# ph_for_cadizv41_pcbv0.net
KiCad netlist of a schematic drawn in EAGLE
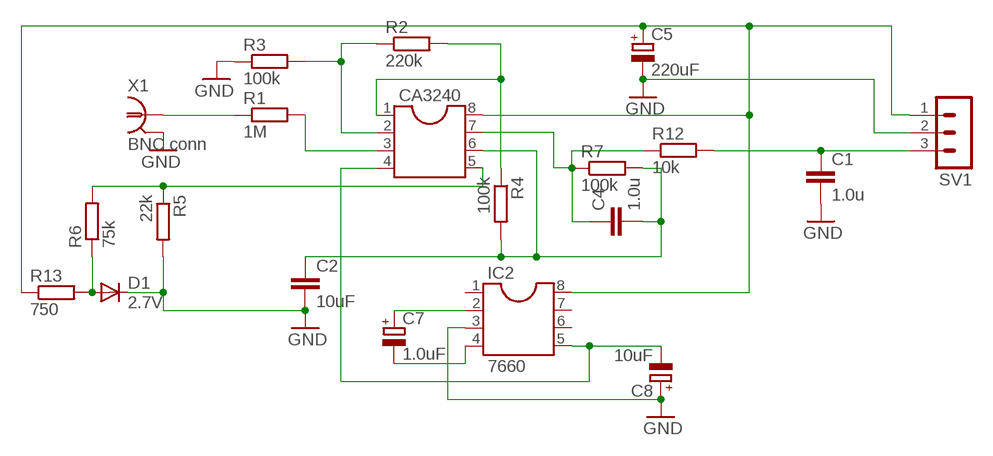
[diagram p0: schematic, sheet 1]

(export (version "E")
  (design (tool "Eeschema 10.0.6"))
  (components
    (comp (ref "C1")
      (value "1.0u")
      (footprint "eagle-import:C102-043X133")
      (libsource (lib "eagle-import") (part "C-EU102-043X133"))
    )
    (comp (ref "C2")
      (value "10uF")
      (footprint "eagle-import:C102-043X133")
      (libsource (lib "eagle-import") (part "C-EU102-043X133"))
    )
    (comp (ref "C4")
      (value "1.0u")
      (footprint "eagle-import:C102-043X133")
      (libsource (lib "eagle-import") (part "C-EU102-043X133"))
    )
    (comp (ref "C5")
      (value "220uF")
      (footprint "eagle-import:E5-6")
      (libsource (lib "eagle-import") (part "CPOL-EUE5-6"))
    )
    (comp (ref "C7")
      (value "1.0uF")
      (footprint "eagle-import:E5-6")
      (libsource (lib "eagle-import") (part "CPOL-EUE5-6"))
    )
    (comp (ref "C8")
      (value "10uF")
      (footprint "eagle-import:E5-6")
      (libsource (lib "eagle-import") (part "CPOL-EUE5-6"))
    )
    (comp (ref "CA3240")
      (value "DIL8")
      (footprint "eagle-import:DIL08")
      (libsource (lib "eagle-import") (part "DIL8"))
    )
    (comp (ref "D1")
      (value "2.7V")
      (footprint "eagle-import:DO35-7")
      (libsource (lib "eagle-import") (part "1N4148DO35-7"))
    )
    (comp (ref "IC2")
      (value "7660")
      (footprint "eagle-import:DIL08")
      (libsource (lib "eagle-import") (part "DIL8"))
    )
    (comp (ref "R1")
      (value "1M")
      (footprint "eagle-import:0207_12")
      (libsource (lib "eagle-import") (part "R-EU_0207/12"))
    )
    (comp (ref "R2")
      (value "220k")
      (footprint "eagle-import:0207_12")
      (libsource (lib "eagle-import") (part "R-EU_0207/12"))
    )
    (comp (ref "R3")
      (value "100k")
      (footprint "eagle-import:0207_12")
      (libsource (lib "eagle-import") (part "R-EU_0207/12"))
    )
    (comp (ref "R4")
      (value "100k")
      (footprint "eagle-import:0207_12")
      (libsource (lib "eagle-import") (part "R-EU_0207/12"))
    )
    (comp (ref "R5")
      (value "22k")
      (footprint "eagle-import:0207_12")
      (libsource (lib "eagle-import") (part "R-EU_0207/12"))
    )
    (comp (ref "R6")
      (value "75k")
      (footprint "eagle-import:0207_12")
      (libsource (lib "eagle-import") (part "R-EU_0207/12"))
    )
    (comp (ref "R7")
      (value "100k")
      (footprint "eagle-import:0207_12")
      (libsource (lib "eagle-import") (part "R-EU_0207/12"))
    )
    (comp (ref "R12")
      (value "10k")
      (footprint "eagle-import:0207_12")
      (libsource (lib "eagle-import") (part "R-EU_0207/12"))
    )
    (comp (ref "R13")
      (value "750")
      (footprint "eagle-import:0207_12")
      (libsource (lib "eagle-import") (part "R-EU_0207/12"))
    )
    (comp (ref "SV1")
      (value "MA03-1")
      (footprint "eagle-import:MA03-1")
      (libsource (lib "eagle-import") (part "MA03-1"))
    )
    (comp (ref "X1")
      (value "BNC conn")
      (footprint "eagle-import:R141426")
      (fields (field (name "MF") "FARNELL") (field (name "MPN") "R141426161"))
      (libsource (lib "eagle-import") (part "R141426"))
    )
  )
  (nets
    (net (code "1") (name "GND") (class "Default")
      (node (ref "C1") (pin "2") (pinfunction "2_2") (pintype "passive"))
      (node (ref "C2") (pin "2") (pinfunction "2_2") (pintype "passive"))
      (node (ref "C5") (pin "-") (pinfunction "-_-") (pintype "passive"))
      (node (ref "C8") (pin "+") (pinfunction "+_+") (pintype "passive"))
      (node (ref "D1") (pin "C") (pinfunction "C_C") (pintype "passive"))
      (node (ref "IC2") (pin "3") (pinfunction "3_3") (pintype "passive"))
      (node (ref "R3") (pin "1") (pinfunction "1_1") (pintype "passive"))
      (node (ref "R5") (pin "2") (pinfunction "2_2") (pintype "passive"))
      (node (ref "SV1") (pin "2") (pinfunction "2_2") (pintype "passive"))
      (node (ref "X1") (pin "2") (pinfunction "GND_2") (pintype "power_in"))
    )
    (net (code "2") (name "Net-(C1-Pad1)") (class "Default")
      (node (ref "C1") (pin "1") (pinfunction "1_1") (pintype "passive"))
      (node (ref "R12") (pin "2") (pinfunction "2_2") (pintype "passive"))
      (node (ref "SV1") (pin "3") (pinfunction "3_3") (pintype "passive"))
    )
    (net (code "3") (name "Net-(C2-Pad1)") (class "Default")
      (node (ref "C2") (pin "1") (pinfunction "1_1") (pintype "passive"))
      (node (ref "C4") (pin "2") (pinfunction "2_2") (pintype "passive"))
      (node (ref "CA3240") (pin "6") (pinfunction "6_6") (pintype "passive"))
      (node (ref "R4") (pin "2") (pinfunction "2_2") (pintype "passive"))
      (node (ref "R7") (pin "2") (pinfunction "2_2") (pintype "passive"))
    )
    (net (code "4") (name "Net-(C4-Pad1)") (class "Default")
      (node (ref "C4") (pin "1") (pinfunction "1_1") (pintype "passive"))
      (node (ref "CA3240") (pin "7") (pinfunction "7_7") (pintype "passive"))
      (node (ref "R12") (pin "1") (pinfunction "1_1") (pintype "passive"))
      (node (ref "R7") (pin "1") (pinfunction "1_1") (pintype "passive"))
    )
    (net (code "5") (name "Net-(C5-Pad+)") (class "Default")
      (node (ref "C5") (pin "+") (pinfunction "+_+") (pintype "passive"))
      (node (ref "CA3240") (pin "8") (pinfunction "8_8") (pintype "passive"))
      (node (ref "IC2") (pin "8") (pinfunction "8_8") (pintype "passive"))
      (node (ref "R13") (pin "1") (pinfunction "1_1") (pintype "passive"))
      (node (ref "SV1") (pin "1") (pinfunction "1_1") (pintype "passive"))
    )
    (net (code "6") (name "Net-(C7-Pad+)") (class "Default")
      (node (ref "C7") (pin "+") (pinfunction "+_+") (pintype "passive"))
      (node (ref "IC2") (pin "2") (pinfunction "2_2") (pintype "passive"))
    )
    (net (code "7") (name "Net-(C7-Pad-)") (class "Default")
      (node (ref "C7") (pin "-") (pinfunction "-_-") (pintype "passive"))
      (node (ref "IC2") (pin "4") (pinfunction "4_4") (pintype "passive"))
    )
    (net (code "8") (name "Net-(C8-Pad-)") (class "Default")
      (node (ref "C8") (pin "-") (pinfunction "-_-") (pintype "passive"))
      (node (ref "CA3240") (pin "4") (pinfunction "4_4") (pintype "passive"))
      (node (ref "IC2") (pin "5") (pinfunction "5_5") (pintype "passive"))
    )
    (net (code "9") (name "Net-(CA3240-Pad1)") (class "Default")
      (node (ref "CA3240") (pin "1") (pinfunction "1_1") (pintype "passive"))
      (node (ref "R2") (pin "2") (pinfunction "2_2") (pintype "passive"))
      (node (ref "R4") (pin "1") (pinfunction "1_1") (pintype "passive"))
    )
    (net (code "10") (name "Net-(CA3240-Pad2)") (class "Default")
      (node (ref "CA3240") (pin "2") (pinfunction "2_2") (pintype "passive"))
      (node (ref "R2") (pin "1") (pinfunction "1_1") (pintype "passive"))
      (node (ref "R3") (pin "2") (pinfunction "2_2") (pintype "passive"))
    )
    (net (code "11") (name "Net-(CA3240-Pad3)") (class "Default")
      (node (ref "CA3240") (pin "3") (pinfunction "3_3") (pintype "passive"))
      (node (ref "R1") (pin "2") (pinfunction "2_2") (pintype "passive"))
    )
    (net (code "12") (name "Net-(CA3240-Pad5)") (class "Default")
      (node (ref "CA3240") (pin "5") (pinfunction "5_5") (pintype "passive"))
      (node (ref "R5") (pin "1") (pinfunction "1_1") (pintype "passive"))
      (node (ref "R6") (pin "2") (pinfunction "2_2") (pintype "passive"))
    )
    (net (code "13") (name "Net-(D1-PadA)") (class "Default")
      (node (ref "D1") (pin "A") (pinfunction "A_A") (pintype "passive"))
      (node (ref "R13") (pin "2") (pinfunction "2_2") (pintype "passive"))
      (node (ref "R6") (pin "1") (pinfunction "1_1") (pintype "passive"))
    )
    (net (code "14") (name "Net-(R1-Pad1)") (class "Default")
      (node (ref "R1") (pin "1") (pinfunction "1_1") (pintype "passive"))
      (node (ref "X1") (pin "1") (pinfunction "1_1") (pintype "passive"))
    )
    (net (code "15") (name "unconnected-(IC2-Pad1)") (class "Default")
      (node (ref "IC2") (pin "1") (pinfunction "1_1") (pintype "passive"))
    )
    (net (code "16") (name "unconnected-(IC2-Pad6)") (class "Default")
      (node (ref "IC2") (pin "6") (pinfunction "6_6") (pintype "passive"))
    )
    (net (code "17") (name "unconnected-(IC2-Pad7)") (class "Default")
      (node (ref "IC2") (pin "7") (pinfunction "7_7") (pintype "passive"))
    )
  )
)
